# DS18B20.net
KiCad netlist of a schematic drawn in Altium Designer
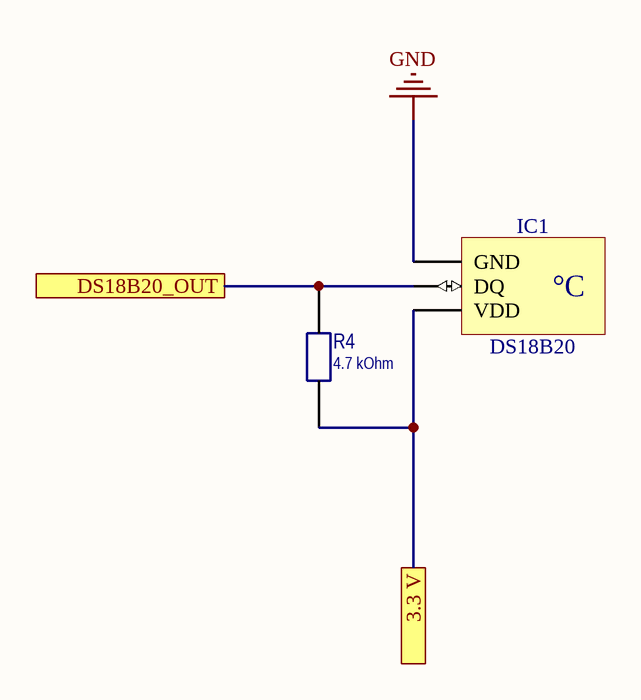
[diagram p0: DS18B20.SchDoc]

(export (version "E")
  (design (tool "Eeschema 10.0.6"))
  (components
    (comp (ref "IC1")
      (value "DS18B20")
      (footprint "DS18B20")
      (description "Programmable Resolution 1-Wire Digital Thermometer")
      (libsource (lib "Sensors") (part "DS18B20+"))
    )
    (comp (ref "R4")
      (value "4.7 kOhm")
      (footprint "R_0805")
      (description "Resistor")
      (libsource (lib "resistors") (part "R0805"))
    )
  )
  (nets
    (net (code "1") (name "/3.3 V") (class "Default")
      (node (ref "IC1") (pin "3") (pinfunction "VDD_3") (pintype "power_in"))
      (node (ref "R4") (pin "1") (pinfunction "1_1") (pintype "passive"))
    )
    (net (code "2") (name "/DS18B20_OUT") (class "Default")
      (node (ref "IC1") (pin "2") (pinfunction "DQ_2") (pintype "bidirectional"))
      (node (ref "R4") (pin "2") (pinfunction "2_2") (pintype "passive"))
    )
    (net (code "3") (name "GND") (class "Default")
      (node (ref "IC1") (pin "1") (pinfunction "GND_1") (pintype "power_in"))
    )
  )
)
